# 4_-Driver.net
KiCad netlist of a schematic drawn in Altium Designer
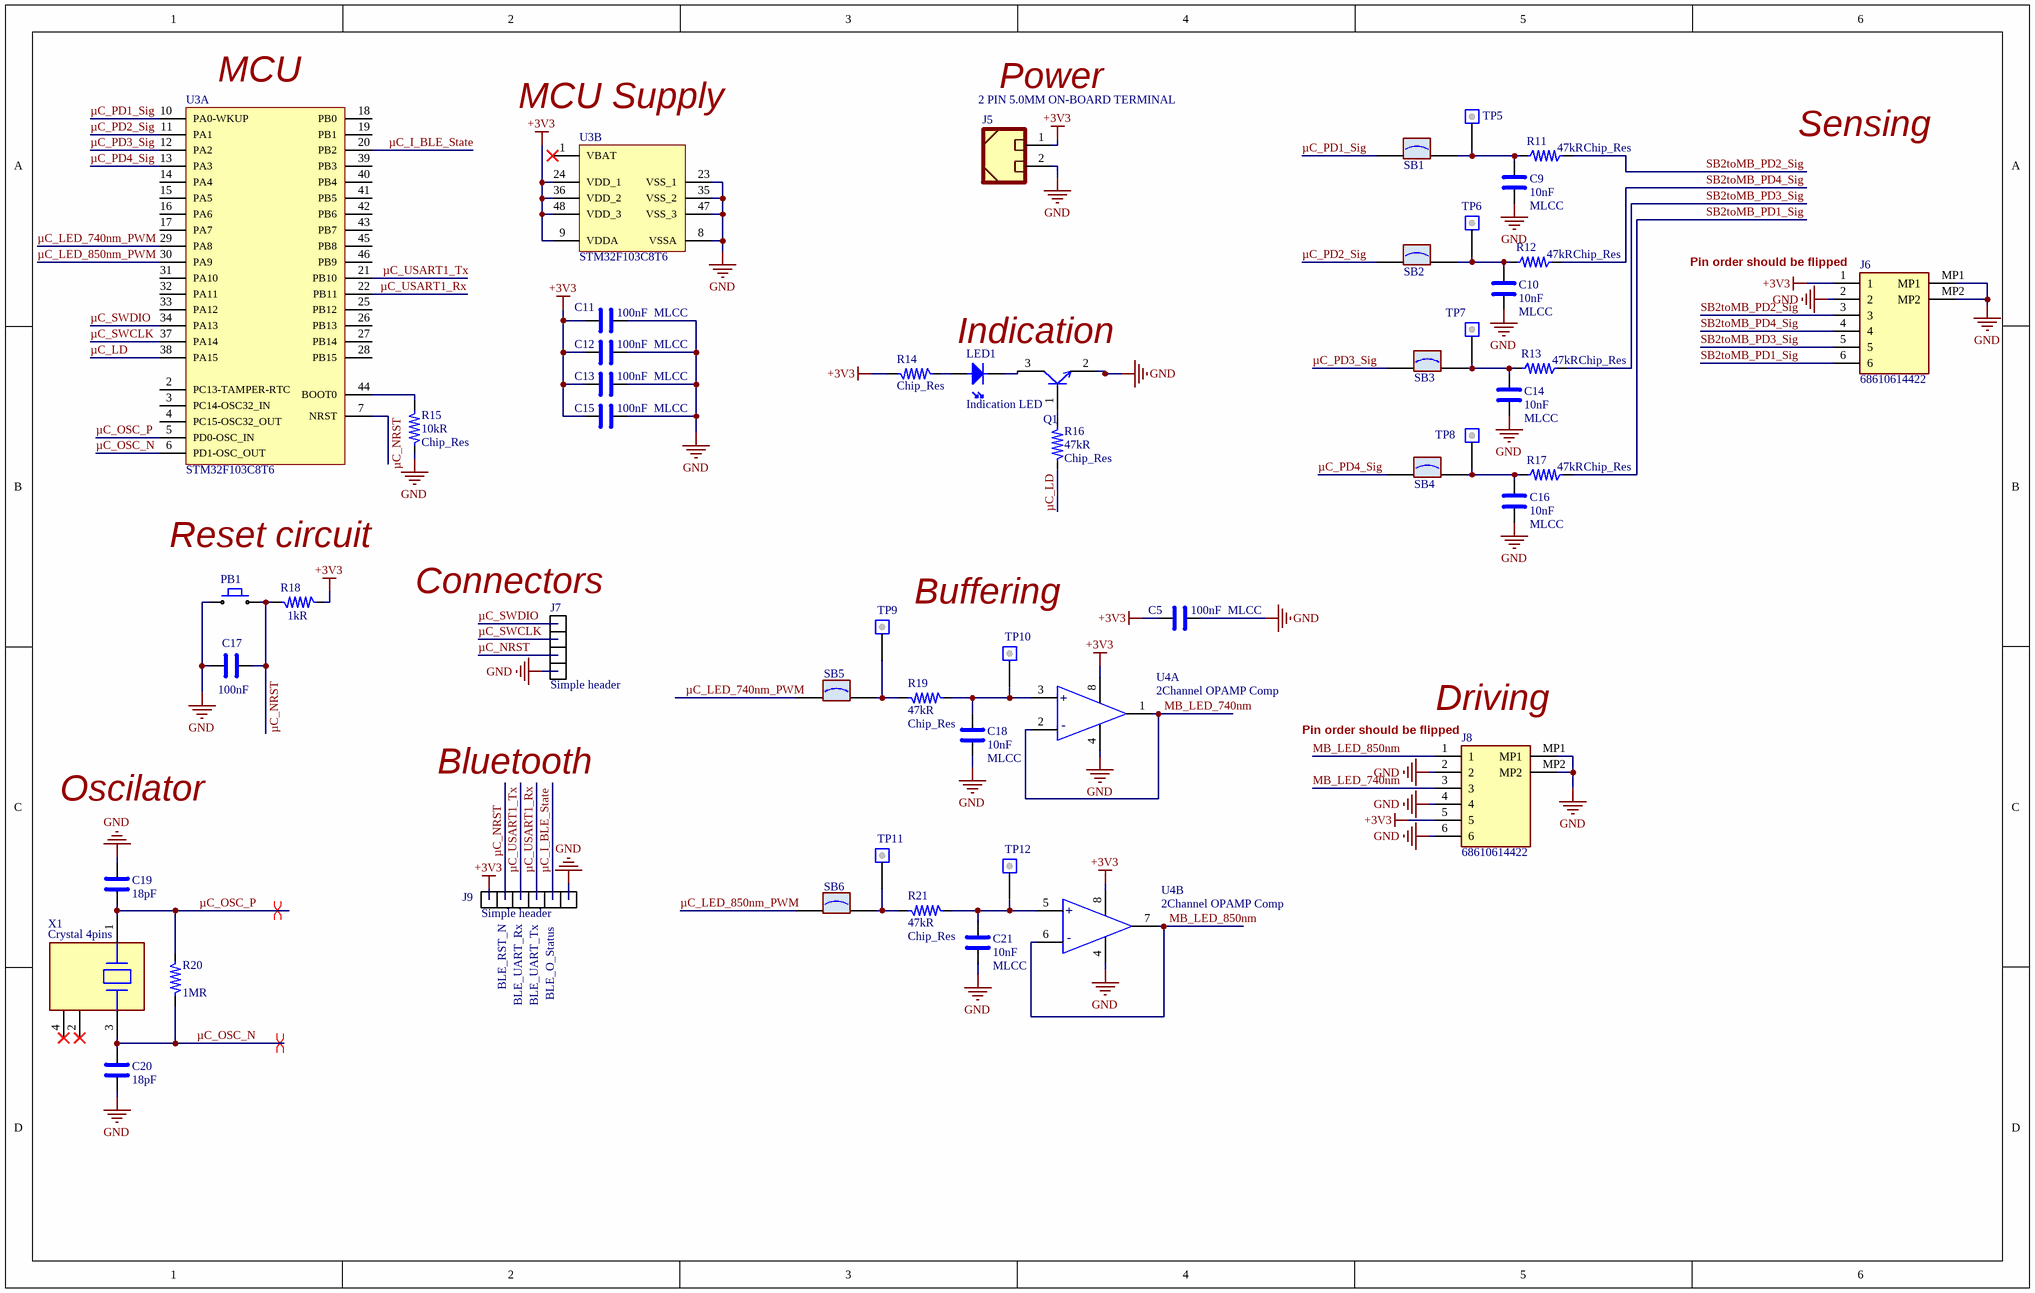
[diagram p0: [4]-Driver.SchDoc]

(export (version "E")
  (design (tool "Eeschema 10.0.6"))
  (components
    (comp (ref "C5")
      (value "MLCC")
      (footprint "CAPC1608X09M")
      (description "Multilayer Ceramic Capacitor, 0.1 uF, 50 V, ± 10%, X7R, 0603 [1608 Metric]")
      (fields
        (field (name "PART NUMBER") "GCM188R71H104KA57D")
        (field (name "ALTIUM_VALUE") "100nF")
        (field (name "MANUFACTURER") "Murata")
      )
      (libsource (lib "Capacitors") (part "MLCC"))
    )
    (comp (ref "C9")
      (value "MLCC")
      (footprint "CAPC1005X06M")
      (description "Multilayer Ceramic Capacitor, 0.01 uF, 25 V, ± 10%, X7R, 0402 [1005 Metric]")
      (fields
        (field (name "PART NUMBER") "GRM155R71E103KA01D")
        (field (name "ALTIUM_VALUE") "10nF")
        (field (name "MANUFACTURER") "Murata")
      )
      (libsource (lib "Capacitors") (part "MLCC"))
    )
    (comp (ref "C10")
      (value "MLCC")
      (footprint "CAPC1005X06M")
      (description "Multilayer Ceramic Capacitor, 0.01 uF, 25 V, ± 10%, X7R, 0402 [1005 Metric]")
      (fields
        (field (name "PART NUMBER") "GRM155R71E103KA01D")
        (field (name "ALTIUM_VALUE") "10nF")
        (field (name "MANUFACTURER") "Murata")
      )
      (libsource (lib "Capacitors") (part "MLCC"))
    )
    (comp (ref "C11")
      (value "MLCC")
      (footprint "CAPC1608X09M")
      (description "Multilayer Ceramic Capacitor, 0.1 uF, 50 V, ± 10%, X7R, 0603 [1608 Metric]")
      (fields
        (field (name "PART NUMBER") "GCM188R71H104KA57D")
        (field (name "ALTIUM_VALUE") "100nF")
        (field (name "MANUFACTURER") "Murata")
      )
      (libsource (lib "Capacitors") (part "MLCC"))
    )
    (comp (ref "C12")
      (value "MLCC")
      (footprint "CAPC1608X09M")
      (description "Multilayer Ceramic Capacitor, 0.1 uF, 50 V, ± 10%, X7R, 0603 [1608 Metric]")
      (fields
        (field (name "PART NUMBER") "GCM188R71H104KA57D")
        (field (name "ALTIUM_VALUE") "100nF")
        (field (name "MANUFACTURER") "Murata")
      )
      (libsource (lib "Capacitors") (part "MLCC"))
    )
    (comp (ref "C13")
      (value "MLCC")
      (footprint "CAPC1608X09M")
      (description "Multilayer Ceramic Capacitor, 0.1 uF, 50 V, ± 10%, X7R, 0603 [1608 Metric]")
      (fields
        (field (name "PART NUMBER") "GCM188R71H104KA57D")
        (field (name "ALTIUM_VALUE") "100nF")
        (field (name "MANUFACTURER") "Murata")
      )
      (libsource (lib "Capacitors") (part "MLCC"))
    )
    (comp (ref "C14")
      (value "MLCC")
      (footprint "CAPC1005X06M")
      (description "Multilayer Ceramic Capacitor, 0.01 uF, 25 V, ± 10%, X7R, 0402 [1005 Metric]")
      (fields
        (field (name "PART NUMBER") "GRM155R71E103KA01D")
        (field (name "ALTIUM_VALUE") "10nF")
        (field (name "MANUFACTURER") "Murata")
      )
      (libsource (lib "Capacitors") (part "MLCC"))
    )
    (comp (ref "C15")
      (value "MLCC")
      (footprint "CAPC1608X09M")
      (description "Multilayer Ceramic Capacitor, 0.1 uF, 50 V, ± 10%, X7R, 0603 [1608 Metric]")
      (fields
        (field (name "PART NUMBER") "GCM188R71H104KA57D")
        (field (name "ALTIUM_VALUE") "100nF")
        (field (name "MANUFACTURER") "Murata")
      )
      (libsource (lib "Capacitors") (part "MLCC"))
    )
    (comp (ref "C16")
      (value "MLCC")
      (footprint "CAPC1005X06M")
      (description "Multilayer Ceramic Capacitor, 0.01 uF, 25 V, ± 10%, X7R, 0402 [1005 Metric]")
      (fields
        (field (name "PART NUMBER") "GRM155R71E103KA01D")
        (field (name "ALTIUM_VALUE") "10nF")
        (field (name "MANUFACTURER") "Murata")
      )
      (libsource (lib "Capacitors") (part "MLCC"))
    )
    (comp (ref "C17")
      (value "100nF")
      (footprint "CAPC1005X06L")
      (description "Multilayer Ceramic Capacitor, 0.1 uF, 16 V, ± 10%, X7R, 0402 [1005 Metric]")
      (fields (field (name "PART NUMBER") "GRM155R71C104KA88J") (field (name "MANUFACTURER") "Murata"))
      (libsource (lib "Capacitors") (part "MLCC"))
    )
    (comp (ref "C18")
      (value "MLCC")
      (footprint "CAPC1005X06M")
      (description "Multilayer Ceramic Capacitor, 0.01 uF, 25 V, ± 10%, X7R, 0402 [1005 Metric]")
      (fields
        (field (name "PART NUMBER") "GRM155R71E103KA01D")
        (field (name "ALTIUM_VALUE") "10nF")
        (field (name "MANUFACTURER") "Murata")
      )
      (libsource (lib "Capacitors") (part "MLCC"))
    )
    (comp (ref "C19")
      (value "18pF")
      (footprint "CAPC1005X06L")
      (description "Multilayer Ceramic Capacitor, 18 pF, 50 V, ± 5%, C0G (NP0), 0402 [1005 Metric]")
      (fields (field (name "PART NUMBER") "GRM1555C1H180JA01D") (field (name "MANUFACTURER") "Murata"))
      (libsource (lib "Capacitors") (part "MLCC"))
    )
    (comp (ref "C20")
      (value "18pF")
      (footprint "CAPC1005X06L")
      (description "Multilayer Ceramic Capacitor, 18 pF, 50 V, ± 5%, C0G (NP0), 0402 [1005 Metric]")
      (fields (field (name "PART NUMBER") "GRM1555C1H180JA01D") (field (name "MANUFACTURER") "Murata"))
      (libsource (lib "Capacitors") (part "MLCC"))
    )
    (comp (ref "C21")
      (value "MLCC")
      (footprint "CAPC1005X06M")
      (description "Multilayer Ceramic Capacitor, 0.01 uF, 25 V, ± 10%, X7R, 0402 [1005 Metric]")
      (fields
        (field (name "PART NUMBER") "GRM155R71E103KA01D")
        (field (name "ALTIUM_VALUE") "10nF")
        (field (name "MANUFACTURER") "Murata")
      )
      (libsource (lib "Capacitors") (part "MLCC"))
    )
    (comp (ref "J5")
      (value "2 PIN 5.0MM ON-BOARD TERMINAL")
      (footprint "KF127-5.0-2P")
      (description "2 Pin 5.0mm on-board terminal")
      (fields
        (field (name "PART NUMBER") "KF127-5.0-2P")
        (field (name "MANUFACTURER") "Cixi Kefa Electronics")
      )
      (libsource (lib "Connector") (part "KF127-5.0-2P"))
    )
    (comp (ref "J6")
      (value "68610614422")
      (footprint "68610614422")
      (description "6 Position FPC Connector Contacts, Bottom 0.039\" (1.00mm) Surface Mount, Right Angle")
      (fields (field (name "MANUFACTURER") "Würth Elektronik"))
      (libsource (lib "Connector") (part "68610614422"))
    )
    (comp (ref "J7")
      (value "Simple header")
      (footprint "FP-Header_4x2_54mm")
      (description "4x2.54mm conventional header as jumper")
      (fields (field (name "PART NUMBER") "Header4x1"))
      (libsource (lib "Connector") (part "Header4x1"))
    )
    (comp (ref "J8")
      (value "68610614422")
      (footprint "68610614422")
      (description "6 Position FPC Connector Contacts, Bottom 0.039\" (1.00mm) Surface Mount, Right Angle")
      (fields (field (name "MANUFACTURER") "Würth Elektronik"))
      (libsource (lib "Connector") (part "68610614422"))
    )
    (comp (ref "J9")
      (value "Simple header")
      (footprint "DS1021-1X6S25")
      (description "6x2.54mm conventional header as jumper")
      (fields (field (name "PART NUMBER") "Header6x1"))
      (libsource (lib "Connector") (part "Header6x1"))
    )
    (comp (ref "LED1")
      (value "Indication LED")
      (footprint "LEDC2012X110N")
      (description "LED Uni-Color Green 574nm 2-Pin Chip LED T/R")
      (fields (field (name "PART NUMBER") "LTST-C170KGKT") (field (name "MANUFACTURER") "Vishay Lite-On"))
      (libsource (lib "Diodes") (part "Indication LED"))
    )
    (comp (ref "PB1")
      (value "SWITCH TACTILE SPST-NO 0.05A 12V")
      (footprint "FP-PB_SMD")
      (description "Tactile Switch SPST-NO Top Actuated Surface Mount")
      (fields
        (field (name "PART NUMBER") "TS09-63-25-R-260-SMT-TR")
        (field (name "MANUFACTURER PART NUMBER") "CUI Devices")
      )
      (libsource (lib "ElectroMechanical") (part "Tactile Switch"))
    )
    (comp (ref "Q1")
      (value "NPN 45V 0.5A")
      (footprint "SOT65P210X110-3M")
      (description "Bipolar (BJT) Transistor NPN 45 V 500 mA 100MHz 200 mW Surface Mount SOT-323")
      (fields (field (name "PART NUMBER") "BC817-40W,115") (field (name "MANUFACTURER") "Nexperia"))
      (libsource (lib "Transistor") (part "singleBJT_NPN"))
    )
    (comp (ref "R11")
      (value "Chip_Res")
      (footprint "RESC1005X04M")
      (description "SMD Chip Resistor, 47 kOhm, ± 5%, 63 mW, 0402 [1005 Metric], Thick Film, General Purpose")
      (fields
        (field (name "PART NUMBER") "RC0402JR-0747KL")
        (field (name "ALTIUM_VALUE") "47kR")
        (field (name "MANUFACTURER") "Yageo")
      )
      (libsource (lib "Resistors") (part "Chip_Res"))
    )
    (comp (ref "R12")
      (value "Chip_Res")
      (footprint "RESC1005X04M")
      (description "SMD Chip Resistor, 47 kOhm, ± 5%, 63 mW, 0402 [1005 Metric], Thick Film, General Purpose")
      (fields
        (field (name "PART NUMBER") "RC0402JR-0747KL")
        (field (name "ALTIUM_VALUE") "47kR")
        (field (name "MANUFACTURER") "Yageo")
      )
      (libsource (lib "Resistors") (part "Chip_Res"))
    )
    (comp (ref "R13")
      (value "Chip_Res")
      (footprint "RESC1005X04M")
      (description "SMD Chip Resistor, 47 kOhm, ± 5%, 63 mW, 0402 [1005 Metric], Thick Film, General Purpose")
      (fields
        (field (name "PART NUMBER") "RC0402JR-0747KL")
        (field (name "ALTIUM_VALUE") "47kR")
        (field (name "MANUFACTURER") "Yageo")
      )
      (libsource (lib "Resistors") (part "Chip_Res"))
    )
    (comp (ref "R14")
      (value "Chip_Res")
      (footprint "RESC1608X06M")
      (description "SMD Chip Resistor, 470 Ohm, ± 1%, 100 mW, 0603 [1608 Metric], Thick Film, General Purpose")
      (fields (field (name "PART NUMBER") "RC0603FR-07470RL") (field (name "MANUFACTURER") "Yageo"))
      (libsource (lib "Resistors") (part "Chip_Res"))
    )
    (comp (ref "R15")
      (value "Chip_Res")
      (footprint "RESC1005X04M")
      (description "SMD Chip Resistor, 10 kOhm, ± 5%, 63 mW, 0402 [1005 Metric], Thick Film, General Purpose")
      (fields
        (field (name "PART NUMBER") "RC0402JR-0710KL")
        (field (name "ALTIUM_VALUE") "10kR")
        (field (name "MANUFACTURER") "Yageo")
      )
      (libsource (lib "Resistors") (part "Chip_Res"))
    )
    (comp (ref "R16")
      (value "Chip_Res")
      (footprint "RESC1005X04M")
      (description "SMD Chip Resistor, 47 kOhm, ± 5%, 63 mW, 0402 [1005 Metric], Thick Film, General Purpose")
      (fields
        (field (name "PART NUMBER") "RC0402JR-0747KL")
        (field (name "ALTIUM_VALUE") "47kR")
        (field (name "MANUFACTURER") "Yageo")
      )
      (libsource (lib "Resistors") (part "Chip_Res"))
    )
    (comp (ref "R17")
      (value "Chip_Res")
      (footprint "RESC1005X04M")
      (description "SMD Chip Resistor, 47 kOhm, ± 5%, 63 mW, 0402 [1005 Metric], Thick Film, General Purpose")
      (fields
        (field (name "PART NUMBER") "RC0402JR-0747KL")
        (field (name "ALTIUM_VALUE") "47kR")
        (field (name "MANUFACTURER") "Yageo")
      )
      (libsource (lib "Resistors") (part "Chip_Res"))
    )
    (comp (ref "R18")
      (value "1kR")
      (footprint "RESC1005X04L")
      (description "SMD Chip Resistor, 1 kOhm, ± 5%, 63 mW, 0402 [1005 Metric], Thick Film, General Purpose")
      (fields (field (name "PART NUMBER") "RC0402JR-071KL") (field (name "MANUFACTURER") "Yageo"))
      (libsource (lib "Resistors") (part "Chip_Res"))
    )
    (comp (ref "R19")
      (value "Chip_Res")
      (footprint "RESC1005X04M")
      (description "SMD Chip Resistor, 47 kOhm, ± 5%, 63 mW, 0402 [1005 Metric], Thick Film, General Purpose")
      (fields
        (field (name "PART NUMBER") "RC0402JR-0747KL")
        (field (name "ALTIUM_VALUE") "47kR")
        (field (name "MANUFACTURER") "Yageo")
      )
      (libsource (lib "Resistors") (part "Chip_Res"))
    )
    (comp (ref "R20")
      (value "1MR")
      (footprint "RESC1005X04L")
      (description "SMD Chip Resistor, 1 MOhm, ± 5%, 63 mW, 0402 [1005 Metric], Thick Film, General Purpose")
      (fields (field (name "PART NUMBER") "RC0402JR-071ML") (field (name "MANUFACTURER") "Yageo"))
      (libsource (lib "Resistors") (part "Chip_Res"))
    )
    (comp (ref "R21")
      (value "Chip_Res")
      (footprint "RESC1005X04M")
      (description "SMD Chip Resistor, 47 kOhm, ± 5%, 63 mW, 0402 [1005 Metric], Thick Film, General Purpose")
      (fields
        (field (name "PART NUMBER") "RC0402JR-0747KL")
        (field (name "ALTIUM_VALUE") "47kR")
        (field (name "MANUFACTURER") "Yageo")
      )
      (libsource (lib "Resistors") (part "Chip_Res"))
    )
    (comp (ref "SB1")
      (value "SB")
      (footprint "FP-SB_0_8mm")
      (description "A simple solder bridge")
      (fields (field (name "PART NUMBER") "Solder Bridge"))
      (libsource (lib "Miscellaneous") (part "SB"))
    )
    (comp (ref "SB2")
      (value "SB")
      (footprint "FP-SB_0_8mm")
      (description "A simple solder bridge")
      (fields (field (name "PART NUMBER") "Solder Bridge"))
      (libsource (lib "Miscellaneous") (part "SB"))
    )
    (comp (ref "SB3")
      (value "SB")
      (footprint "FP-SB_0_8mm")
      (description "A simple solder bridge")
      (fields (field (name "PART NUMBER") "Solder Bridge"))
      (libsource (lib "Miscellaneous") (part "SB"))
    )
    (comp (ref "SB4")
      (value "SB")
      (footprint "FP-SB_0_8mm")
      (description "A simple solder bridge")
      (fields (field (name "PART NUMBER") "Solder Bridge"))
      (libsource (lib "Miscellaneous") (part "SB"))
    )
    (comp (ref "SB5")
      (value "SB")
      (footprint "FP-SB_0_8mm")
      (description "A simple solder bridge")
      (fields (field (name "PART NUMBER") "Solder Bridge"))
      (libsource (lib "") (part "SB_1"))
    )
    (comp (ref "SB6")
      (value "SB")
      (footprint "FP-SB_0_8mm")
      (description "A simple solder bridge")
      (fields (field (name "PART NUMBER") "Solder Bridge"))
      (libsource (lib "") (part "SB_1"))
    )
    (comp (ref "TP5")
      (value "TP")
      (footprint "FP-TP_DIP")
      (description "A simple test point")
      (fields (field (name "PART NUMBER") "Test Point"))
      (libsource (lib "Miscellaneous") (part "TP"))
    )
    (comp (ref "TP6")
      (value "TP")
      (footprint "FP-TP_DIP")
      (description "A simple test point")
      (fields (field (name "PART NUMBER") "Test Point"))
      (libsource (lib "Miscellaneous") (part "TP"))
    )
    (comp (ref "TP7")
      (value "TP")
      (footprint "FP-TP_DIP")
      (description "A simple test point")
      (fields (field (name "PART NUMBER") "Test Point"))
      (libsource (lib "Miscellaneous") (part "TP"))
    )
    (comp (ref "TP8")
      (value "TP")
      (footprint "FP-TP_DIP")
      (description "A simple test point")
      (fields (field (name "PART NUMBER") "Test Point"))
      (libsource (lib "Miscellaneous") (part "TP"))
    )
    (comp (ref "TP9")
      (value "TP")
      (footprint "FP-TP_DIP")
      (description "A simple test point")
      (fields (field (name "PART NUMBER") "Test Point"))
      (libsource (lib "Miscellaneous") (part "TP"))
    )
    (comp (ref "TP10")
      (value "TP")
      (footprint "FP-TP_SMD_Narrow")
      (description "A simple test point")
      (fields (field (name "PART NUMBER") "Test Point"))
      (libsource (lib "Miscellaneous") (part "TP"))
    )
    (comp (ref "TP11")
      (value "TP")
      (footprint "FP-TP_DIP")
      (description "A simple test point")
      (fields (field (name "PART NUMBER") "Test Point"))
      (libsource (lib "Miscellaneous") (part "TP"))
    )
    (comp (ref "TP12")
      (value "TP")
      (footprint "FP-TP_SMD_Narrow")
      (description "A simple test point")
      (fields (field (name "PART NUMBER") "Test Point"))
      (libsource (lib "Miscellaneous") (part "TP"))
    )
    (comp (ref "U3")
      (value "STM32F103C8T6")
      (footprint "STM-LQFP48_N")
      (description "MCU 32-bit STM32F1 ARM Cortex M3 RISC 64KB Flash 2.5V/3.3V 48-Pin LQFP T/R")
      (fields
        (field (name "PART NUMBER") "STM32F103C8T6TR")
        (field (name "MANUFACTURER") "STMicroelectronics")
      )
      (libsource (lib "ICs") (part "STM32F103C8T6"))
    )
    (comp (ref "U4")
      (value "2Channel OPAMP Comp")
      (footprint "SOIC127P600X175-8N")
      (description "CMOS Amplifier 2 Circuit Rail-to-Rail 8-SOIC")
      (fields (field (name "PART NUMBER") "OPA2377AIDR") (field (name "MANUFACTURER") "Texas Instruments"))
      (libsource (lib "ICs") (part "2Channel OPAMP Comp"))
    )
    (comp (ref "X1")
      (value "Crystal 4pins")
      (footprint "FP-ABM8-MFG")
      (description "8 MHz ±10ppm Crystal 18pF 500 Ohms 4-SMD, No Lead")
      (fields (field (name "PART NUMBER") "ABM8AIG-8.000MHZ-1Z-T"))
      (libsource (lib "Crystal_Oscillator") (part "Crystal 4pins"))
    )
  )
  (nets
    (net (code "1") (name "+3V3") (class "Default")
      (node (ref "C11") (pin "1") (pinfunction "1_1") (pintype "passive"))
      (node (ref "C12") (pin "1") (pinfunction "1_1") (pintype "passive"))
      (node (ref "C13") (pin "1") (pinfunction "1_1") (pintype "passive"))
      (node (ref "C15") (pin "1") (pinfunction "1_1") (pintype "passive"))
      (node (ref "C5") (pin "1") (pinfunction "1_1") (pintype "passive"))
      (node (ref "J5") (pin "1") (pinfunction "1_1") (pintype "passive"))
      (node (ref "J6") (pin "1") (pinfunction "1_1") (pintype "passive"))
      (node (ref "J8") (pin "5") (pinfunction "5_5") (pintype "passive"))
      (node (ref "J9") (pin "1") (pinfunction "1_1") (pintype "passive"))
      (node (ref "R14") (pin "1") (pinfunction "1_1") (pintype "passive"))
      (node (ref "R18") (pin "2") (pinfunction "2_2") (pintype "passive"))
      (node (ref "U3") (pin "24") (pinfunction "VDD_1_24") (pintype "passive"))
      (node (ref "U3") (pin "36") (pinfunction "VDD_2_36") (pintype "passive"))
      (node (ref "U3") (pin "48") (pinfunction "VDD_3_48") (pintype "passive"))
      (node (ref "U3") (pin "9") (pinfunction "VDDA_9") (pintype "passive"))
      (node (ref "U4") (pin "8") (pinfunction "VCC_8") (pintype "power_in"))
    )
    (net (code "2") (name "/MB_LED_740nm") (class "Default")
      (node (ref "J8") (pin "3") (pinfunction "3_3") (pintype "passive"))
      (node (ref "U4") (pin "1") (pinfunction "1OUT_1") (pintype "passive"))
      (node (ref "U4") (pin "2") (pinfunction "1IN-_2") (pintype "passive"))
    )
    (net (code "3") (name "/MB_LED_850nm") (class "Default")
      (node (ref "J8") (pin "1") (pinfunction "1_1") (pintype "passive"))
      (node (ref "U4") (pin "6") (pinfunction "2IN-_6") (pintype "passive"))
      (node (ref "U4") (pin "7") (pinfunction "2OUT_7") (pintype "passive"))
    )
    (net (code "4") (name "/SB2toMB_PD1_Sig") (class "Default")
      (node (ref "J6") (pin "6") (pinfunction "6_6") (pintype "passive"))
      (node (ref "R17") (pin "1") (pinfunction "1_1") (pintype "passive"))
    )
    (net (code "5") (name "/SB2toMB_PD2_Sig") (class "Default")
      (node (ref "J6") (pin "3") (pinfunction "3_3") (pintype "passive"))
      (node (ref "R11") (pin "1") (pinfunction "1_1") (pintype "passive"))
    )
    (net (code "6") (name "/SB2toMB_PD3_Sig") (class "Default")
      (node (ref "J6") (pin "5") (pinfunction "5_5") (pintype "passive"))
      (node (ref "R13") (pin "1") (pinfunction "1_1") (pintype "passive"))
    )
    (net (code "7") (name "/SB2toMB_PD4_Sig") (class "Default")
      (node (ref "J6") (pin "4") (pinfunction "4_4") (pintype "passive"))
      (node (ref "R12") (pin "1") (pinfunction "1_1") (pintype "passive"))
    )
    (net (code "8") (name "/µC_I_BLE_State") (class "Default")
      (node (ref "J9") (pin "5") (pinfunction "5_5") (pintype "passive"))
      (node (ref "U3") (pin "20") (pinfunction "PB2_20") (pintype "passive"))
    )
    (net (code "9") (name "/µC_LD") (class "Default")
      (node (ref "R16") (pin "2") (pinfunction "2_2") (pintype "passive"))
      (node (ref "U3") (pin "38") (pinfunction "PA15_38") (pintype "passive"))
    )
    (net (code "10") (name "/µC_LED_740nm_PWM") (class "Default")
      (node (ref "SB5") (pin "1") (pinfunction "1_1") (pintype "passive"))
      (node (ref "U3") (pin "29") (pinfunction "PA8_29") (pintype "passive"))
    )
    (net (code "11") (name "/µC_LED_850nm_PWM") (class "Default")
      (node (ref "SB6") (pin "1") (pinfunction "1_1") (pintype "passive"))
      (node (ref "U3") (pin "30") (pinfunction "PA9_30") (pintype "passive"))
    )
    (net (code "12") (name "/µC_NRST") (class "Default")
      (node (ref "C17") (pin "2") (pinfunction "2_2") (pintype "passive"))
      (node (ref "J7") (pin "3") (pinfunction "3_3") (pintype "passive"))
      (node (ref "J9") (pin "2") (pinfunction "2_2") (pintype "passive"))
      (node (ref "PB1") (pin "2") (pinfunction "2_2") (pintype "passive"))
      (node (ref "R18") (pin "1") (pinfunction "1_1") (pintype "passive"))
      (node (ref "U3") (pin "7") (pinfunction "NRST_7") (pintype "passive"))
    )
    (net (code "13") (name "/µC_OSC_N") (class "Default")
      (node (ref "C20") (pin "2") (pinfunction "2_2") (pintype "passive"))
      (node (ref "R20") (pin "1") (pinfunction "1_1") (pintype "passive"))
      (node (ref "U3") (pin "6") (pinfunction "PD1-OSC_OUT_6") (pintype "passive"))
      (node (ref "X1") (pin "3") (pinfunction "3_3") (pintype "passive"))
    )
    (net (code "14") (name "/µC_OSC_P") (class "Default")
      (node (ref "C19") (pin "1") (pinfunction "1_1") (pintype "passive"))
      (node (ref "R20") (pin "2") (pinfunction "2_2") (pintype "passive"))
      (node (ref "U3") (pin "5") (pinfunction "PD0-OSC_IN_5") (pintype "passive"))
      (node (ref "X1") (pin "1") (pinfunction "1_1") (pintype "passive"))
    )
    (net (code "15") (name "/µC_PD1_Sig") (class "Default")
      (node (ref "SB1") (pin "2") (pinfunction "2_2") (pintype "passive"))
      (node (ref "U3") (pin "10") (pinfunction "PA0-WKUP_10") (pintype "passive"))
    )
    (net (code "16") (name "/µC_PD2_Sig") (class "Default")
      (node (ref "SB2") (pin "2") (pinfunction "2_2") (pintype "passive"))
      (node (ref "U3") (pin "11") (pinfunction "PA1_11") (pintype "passive"))
    )
    (net (code "17") (name "/µC_PD3_Sig") (class "Default")
      (node (ref "SB3") (pin "2") (pinfunction "2_2") (pintype "passive"))
      (node (ref "U3") (pin "12") (pinfunction "PA2_12") (pintype "passive"))
    )
    (net (code "18") (name "/µC_PD4_Sig") (class "Default")
      (node (ref "SB4") (pin "2") (pinfunction "2_2") (pintype "passive"))
      (node (ref "U3") (pin "13") (pinfunction "PA3_13") (pintype "passive"))
    )
    (net (code "19") (name "/µC_SWCLK") (class "Default")
      (node (ref "J7") (pin "2") (pinfunction "2_2") (pintype "passive"))
      (node (ref "U3") (pin "37") (pinfunction "PA14_37") (pintype "passive"))
    )
    (net (code "20") (name "/µC_SWDIO") (class "Default")
      (node (ref "J7") (pin "1") (pinfunction "1_1") (pintype "passive"))
      (node (ref "U3") (pin "34") (pinfunction "PA13_34") (pintype "passive"))
    )
    (net (code "21") (name "/µC_USART1_Rx") (class "Default")
      (node (ref "J9") (pin "4") (pinfunction "4_4") (pintype "passive"))
      (node (ref "U3") (pin "22") (pinfunction "PB11_22") (pintype "passive"))
    )
    (net (code "22") (name "/µC_USART1_Tx") (class "Default")
      (node (ref "J9") (pin "3") (pinfunction "3_3") (pintype "passive"))
      (node (ref "U3") (pin "21") (pinfunction "PB10_21") (pintype "passive"))
    )
    (net (code "23") (name "GND") (class "Default")
      (node (ref "C10") (pin "1") (pinfunction "1_1") (pintype "passive"))
      (node (ref "C11") (pin "2") (pinfunction "2_2") (pintype "passive"))
      (node (ref "C12") (pin "2") (pinfunction "2_2") (pintype "passive"))
      (node (ref "C13") (pin "2") (pinfunction "2_2") (pintype "passive"))
      (node (ref "C14") (pin "1") (pinfunction "1_1") (pintype "passive"))
      (node (ref "C15") (pin "2") (pinfunction "2_2") (pintype "passive"))
      (node (ref "C16") (pin "1") (pinfunction "1_1") (pintype "passive"))
      (node (ref "C17") (pin "1") (pinfunction "1_1") (pintype "passive"))
      (node (ref "C18") (pin "1") (pinfunction "1_1") (pintype "passive"))
      (node (ref "C19") (pin "2") (pinfunction "2_2") (pintype "passive"))
      (node (ref "C20") (pin "1") (pinfunction "1_1") (pintype "passive"))
      (node (ref "C21") (pin "1") (pinfunction "1_1") (pintype "passive"))
      (node (ref "C5") (pin "2") (pinfunction "2_2") (pintype "passive"))
      (node (ref "C9") (pin "1") (pinfunction "1_1") (pintype "passive"))
      (node (ref "J5") (pin "2") (pinfunction "2_2") (pintype "passive"))
      (node (ref "J6") (pin "2") (pinfunction "2_2") (pintype "passive"))
      (node (ref "J6") (pin "MP1") (pinfunction "MP1_MP1") (pintype "passive"))
      (node (ref "J6") (pin "MP2") (pinfunction "MP2_MP2") (pintype "passive"))
      (node (ref "J7") (pin "4") (pinfunction "4_4") (pintype "passive"))
      (node (ref "J8") (pin "2") (pinfunction "2_2") (pintype "passive"))
      (node (ref "J8") (pin "4") (pinfunction "4_4") (pintype "passive"))
      (node (ref "J8") (pin "6") (pinfunction "6_6") (pintype "passive"))
      (node (ref "J8") (pin "MP1") (pinfunction "MP1_MP1") (pintype "passive"))
      (node (ref "J8") (pin "MP2") (pinfunction "MP2_MP2") (pintype "passive"))
      (node (ref "J9") (pin "6") (pinfunction "6_6") (pintype "passive"))
      (node (ref "PB1") (pin "1") (pinfunction "1_1") (pintype "passive"))
      (node (ref "Q1") (pin "2") (pinfunction "Emitter_2") (pintype "passive"))
      (node (ref "R15") (pin "2") (pinfunction "2_2") (pintype "passive"))
      (node (ref "U3") (pin "23") (pinfunction "VSS_1_23") (pintype "passive"))
      (node (ref "U3") (pin "35") (pinfunction "VSS_2_35") (pintype "passive"))
      (node (ref "U3") (pin "47") (pinfunction "VSS_3_47") (pintype "passive"))
      (node (ref "U3") (pin "8") (pinfunction "VSSA_8") (pintype "passive"))
      (node (ref "U4") (pin "4") (pinfunction "GND_4") (pintype "power_in"))
    )
    (net (code "24") (name "Net-(C9-Pad2)") (class "Default")
      (node (ref "C9") (pin "2") (pinfunction "2_2") (pintype "passive"))
      (node (ref "R11") (pin "2") (pinfunction "2_2") (pintype "passive"))
      (node (ref "SB1") (pin "1") (pinfunction "1_1") (pintype "passive"))
      (node (ref "TP5") (pin "NODE") (pinfunction "NODE_NODE") (pintype "passive"))
    )
    (net (code "25") (name "Net-(C10-Pad2)") (class "Default")
      (node (ref "C10") (pin "2") (pinfunction "2_2") (pintype "passive"))
      (node (ref "R12") (pin "2") (pinfunction "2_2") (pintype "passive"))
      (node (ref "SB2") (pin "1") (pinfunction "1_1") (pintype "passive"))
      (node (ref "TP6") (pin "NODE") (pinfunction "NODE_NODE") (pintype "passive"))
    )
    (net (code "26") (name "Net-(C14-Pad2)") (class "Default")
      (node (ref "C14") (pin "2") (pinfunction "2_2") (pintype "passive"))
      (node (ref "R13") (pin "2") (pinfunction "2_2") (pintype "passive"))
      (node (ref "SB3") (pin "1") (pinfunction "1_1") (pintype "passive"))
      (node (ref "TP7") (pin "NODE") (pinfunction "NODE_NODE") (pintype "passive"))
    )
    (net (code "27") (name "Net-(C16-Pad2)") (class "Default")
      (node (ref "C16") (pin "2") (pinfunction "2_2") (pintype "passive"))
      (node (ref "R17") (pin "2") (pinfunction "2_2") (pintype "passive"))
      (node (ref "SB4") (pin "1") (pinfunction "1_1") (pintype "passive"))
      (node (ref "TP8") (pin "NODE") (pinfunction "NODE_NODE") (pintype "passive"))
    )
    (net (code "28") (name "Net-(LED1-Pad1)") (class "Default")
      (node (ref "LED1") (pin "1") (pinfunction "1_1") (pintype "passive"))
      (node (ref "R14") (pin "2") (pinfunction "2_2") (pintype "passive"))
    )
    (net (code "29") (name "Net-(Q1-Base)") (class "Default")
      (node (ref "Q1") (pin "1") (pinfunction "Base_1") (pintype "passive"))
      (node (ref "R16") (pin "1") (pinfunction "1_1") (pintype "passive"))
    )
    (net (code "30") (name "Net-(Q1-Collector)") (class "Default")
      (node (ref "LED1") (pin "2") (pinfunction "2_2") (pintype "passive"))
      (node (ref "Q1") (pin "3") (pinfunction "Collector_3") (pintype "passive"))
    )
    (net (code "31") (name "Net-(R19-Pad1)") (class "Default")
      (node (ref "R19") (pin "1") (pinfunction "1_1") (pintype "passive"))
      (node (ref "SB5") (pin "2") (pinfunction "2_2") (pintype "passive"))
      (node (ref "TP9") (pin "NODE") (pinfunction "NODE_NODE") (pintype "passive"))
    )
    (net (code "32") (name "Net-(R21-Pad1)") (class "Default")
      (node (ref "R21") (pin "1") (pinfunction "1_1") (pintype "passive"))
      (node (ref "SB6") (pin "2") (pinfunction "2_2") (pintype "passive"))
      (node (ref "TP11") (pin "NODE") (pinfunction "NODE_NODE") (pintype "passive"))
    )
    (net (code "33") (name "Net-(U3A-BOOT0)") (class "Default")
      (node (ref "R15") (pin "1") (pinfunction "1_1") (pintype "passive"))
      (node (ref "U3") (pin "44") (pinfunction "BOOT0_44") (pintype "passive"))
    )
    (net (code "34") (name "Net-(U4A-1IN+)") (class "Default")
      (node (ref "C18") (pin "2") (pinfunction "2_2") (pintype "passive"))
      (node (ref "R19") (pin "2") (pinfunction "2_2") (pintype "passive"))
      (node (ref "TP10") (pin "NODE") (pinfunction "NODE_NODE") (pintype "passive"))
      (node (ref "U4") (pin "3") (pinfunction "1IN+_3") (pintype "passive"))
    )
    (net (code "35") (name "Net-(U4B-2IN+)") (class "Default")
      (node (ref "C21") (pin "2") (pinfunction "2_2") (pintype "passive"))
      (node (ref "R21") (pin "2") (pinfunction "2_2") (pintype "passive"))
      (node (ref "TP12") (pin "NODE") (pinfunction "NODE_NODE") (pintype "passive"))
      (node (ref "U4") (pin "5") (pinfunction "2IN+_5") (pintype "passive"))
    )
    (net (code "36") (name "unconnected-(U3A-PA4-Pad14)") (class "Default")
      (node (ref "U3") (pin "14") (pinfunction "PA4_14") (pintype "passive"))
    )
    (net (code "37") (name "unconnected-(U3A-PA5-Pad15)") (class "Default")
      (node (ref "U3") (pin "15") (pinfunction "PA5_15") (pintype "passive"))
    )
    (net (code "38") (name "unconnected-(U3A-PA6-Pad16)") (class "Default")
      (node (ref "U3") (pin "16") (pinfunction "PA6_16") (pintype "passive"))
    )
    (net (code "39") (name "unconnected-(U3A-PA7-Pad17)") (class "Default")
      (node (ref "U3") (pin "17") (pinfunction "PA7_17") (pintype "passive"))
    )
    (net (code "40") (name "unconnected-(U3A-PA10-Pad31)") (class "Default")
      (node (ref "U3") (pin "31") (pinfunction "PA10_31") (pintype "passive"))
    )
    (net (code "41") (name "unconnected-(U3A-PA11-Pad32)") (class "Default")
      (node (ref "U3") (pin "32") (pinfunction "PA11_32") (pintype "passive"))
    )
    (net (code "42") (name "unconnected-(U3A-PA12-Pad33)") (class "Default")
      (node (ref "U3") (pin "33") (pinfunction "PA12_33") (pintype "passive"))
    )
    (net (code "43") (name "unconnected-(U3A-PB0-Pad18)") (class "Default")
      (node (ref "U3") (pin "18") (pinfunction "PB0_18") (pintype "passive"))
    )
    (net (code "44") (name "unconnected-(U3A-PB1-Pad19)") (class "Default")
      (node (ref "U3") (pin "19") (pinfunction "PB1_19") (pintype "passive"))
    )
    (net (code "45") (name "unconnected-(U3A-PB3-Pad39)") (class "Default")
      (node (ref "U3") (pin "39") (pinfunction "PB3_39") (pintype "passive"))
    )
    (net (code "46") (name "unconnected-(U3A-PB4-Pad40)") (class "Default")
      (node (ref "U3") (pin "40") (pinfunction "PB4_40") (pintype "passive"))
    )
    (net (code "47") (name "unconnected-(U3A-PB5-Pad41)") (class "Default")
      (node (ref "U3") (pin "41") (pinfunction "PB5_41") (pintype "passive"))
    )
    (net (code "48") (name "unconnected-(U3A-PB6-Pad42)") (class "Default")
      (node (ref "U3") (pin "42") (pinfunction "PB6_42") (pintype "passive"))
    )
    (net (code "49") (name "unconnected-(U3A-PB7-Pad43)") (class "Default")
      (node (ref "U3") (pin "43") (pinfunction "PB7_43") (pintype "passive"))
    )
    (net (code "50") (name "unconnected-(U3A-PB8-Pad45)") (class "Default")
      (node (ref "U3") (pin "45") (pinfunction "PB8_45") (pintype "passive"))
    )
    (net (code "51") (name "unconnected-(U3A-PB9-Pad46)") (class "Default")
      (node (ref "U3") (pin "46") (pinfunction "PB9_46") (pintype "passive"))
    )
    (net (code "52") (name "unconnected-(U3A-PB12-Pad25)") (class "Default")
      (node (ref "U3") (pin "25") (pinfunction "PB12_25") (pintype "passive"))
    )
    (net (code "53") (name "unconnected-(U3A-PB13-Pad26)") (class "Default")
      (node (ref "U3") (pin "26") (pinfunction "PB13_26") (pintype "passive"))
    )
    (net (code "54") (name "unconnected-(U3A-PB14-Pad27)") (class "Default")
      (node (ref "U3") (pin "27") (pinfunction "PB14_27") (pintype "passive"))
    )
    (net (code "55") (name "unconnected-(U3A-PB15-Pad28)") (class "Default")
      (node (ref "U3") (pin "28") (pinfunction "PB15_28") (pintype "passive"))
    )
    (net (code "56") (name "unconnected-(U3A-PC13-TAMPER-RTC-Pad2)") (class "Default")
      (node (ref "U3") (pin "2") (pinfunction "PC13-TAMPER-RTC_2") (pintype "passive"))
    )
    (net (code "57") (name "unconnected-(U3A-PC14-OSC32_IN-Pad3)") (class "Default")
      (node (ref "U3") (pin "3") (pinfunction "PC14-OSC32_IN_3") (pintype "passive"))
    )
    (net (code "58") (name "unconnected-(U3A-PC15-OSC32_OUT-Pad4)") (class "Default")
      (node (ref "U3") (pin "4") (pinfunction "PC15-OSC32_OUT_4") (pintype "passive"))
    )
    (net (code "59") (name "unconnected-(U3B-VBAT-Pad1)") (class "Default")
      (node (ref "U3") (pin "1") (pinfunction "VBAT_1") (pintype "passive+no_connect"))
    )
    (net (code "60") (name "unconnected-(X1-Pad2)") (class "Default")
      (node (ref "X1") (pin "2") (pintype "power_in+no_connect"))
    )
    (net (code "61") (name "unconnected-(X1-Pad4)") (class "Default")
      (node (ref "X1") (pin "4") (pintype "power_in+no_connect"))
    )
  )
)
